# smart_home_demo.net
KiCad netlist of a schematic drawn in EAGLE
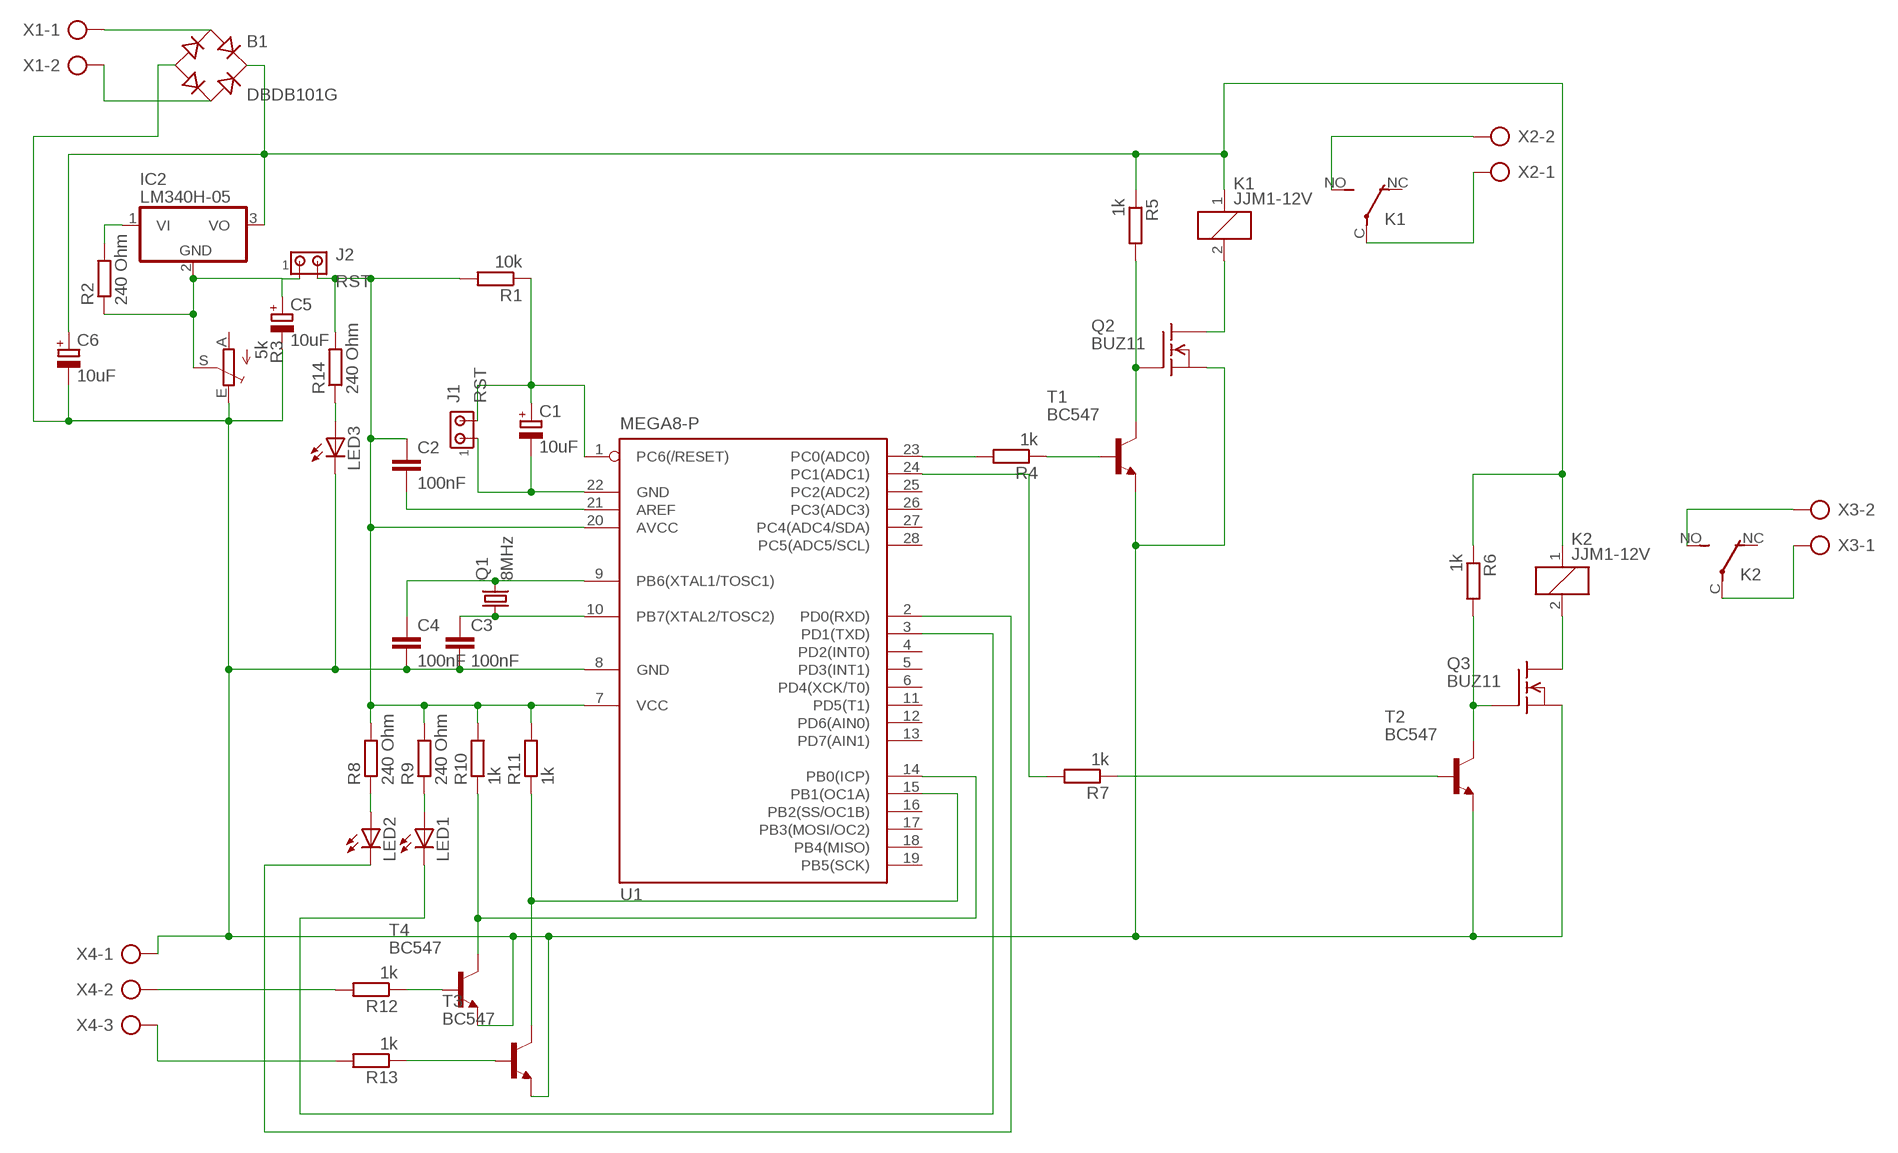
[diagram p0: schematic, sheet 1]

(export (version "E")
  (design (tool "Eeschema 10.0.6"))
  (components
    (comp (ref "B1")
      (value "DBDB101G")
      (footprint "eagle-import:DB")
      (libsource (lib "eagle-import") (part "DB?GDB101"))
    )
    (comp (ref "C1")
      (value "10uF")
      (footprint "eagle-import:E2,5-7")
      (libsource (lib "eagle-import") (part "CPOL-EUE2.5-7"))
    )
    (comp (ref "C2")
      (value "100nF")
      (footprint "eagle-import:C1206K")
      (libsource (lib "eagle-import") (part "C-EUC1206K"))
    )
    (comp (ref "C3")
      (value "100nF")
      (footprint "eagle-import:C1206K")
      (libsource (lib "eagle-import") (part "C-EUC1206K"))
    )
    (comp (ref "C4")
      (value "100nF")
      (footprint "eagle-import:C1206K")
      (libsource (lib "eagle-import") (part "C-EUC1206K"))
    )
    (comp (ref "C5")
      (value "10uF")
      (footprint "eagle-import:E2,5-7")
      (libsource (lib "eagle-import") (part "CPOL-EUE2.5-7"))
    )
    (comp (ref "C6")
      (value "10uF")
      (footprint "eagle-import:E2,5-7")
      (libsource (lib "eagle-import") (part "CPOL-EUE2.5-7"))
    )
    (comp (ref "IC2")
      (value "LM340H-05")
      (footprint "eagle-import:TO220H")
      (libsource (lib "eagle-import") (part "LM340?-H05"))
    )
    (comp (ref "J1")
      (value "RST")
      (footprint "eagle-import:10X02MTA")
      (libsource (lib "eagle-import") (part "MTA02-100"))
    )
    (comp (ref "J2")
      (value "RST")
      (footprint "eagle-import:10X02MTA")
      (libsource (lib "eagle-import") (part "MTA02-100"))
    )
    (comp (ref "K1")
      (value "JJM1-12V")
      (footprint "eagle-import:JJM1C")
      (fields (field (name "MF") "AROMAT/ MATSUSHITA"))
      (libsource (lib "eagle-import") (part "JJM1-12V"))
    )
    (comp (ref "K2")
      (value "JJM1-12V")
      (footprint "eagle-import:JJM1C")
      (fields (field (name "MF") "AROMAT/ MATSUSHITA"))
      (libsource (lib "eagle-import") (part "JJM1-12V"))
    )
    (comp (ref "LED1")
      (value "LED5MM")
      (footprint "eagle-import:LED5MM")
      (libsource (lib "eagle-import") (part "LED5MM"))
    )
    (comp (ref "LED2")
      (value "LED5MM")
      (footprint "eagle-import:LED5MM")
      (libsource (lib "eagle-import") (part "LED5MM"))
    )
    (comp (ref "LED3")
      (value "LED5MM")
      (footprint "eagle-import:LED5MM")
      (libsource (lib "eagle-import") (part "LED5MM"))
    )
    (comp (ref "Q1")
      (value "8MHz")
      (footprint "eagle-import:MC-405")
      (libsource (lib "eagle-import") (part "MC-405"))
    )
    (comp (ref "Q2")
      (value "BUZ11")
      (footprint "eagle-import:TO220")
      (libsource (lib "eagle-import") (part "BUZ11"))
    )
    (comp (ref "Q3")
      (value "BUZ11")
      (footprint "eagle-import:TO220")
      (libsource (lib "eagle-import") (part "BUZ11"))
    )
    (comp (ref "R1")
      (value "10k")
      (footprint "eagle-import:R1206")
      (libsource (lib "eagle-import") (part "R-EU_R1206"))
    )
    (comp (ref "R2")
      (value "240 Ohm")
      (footprint "eagle-import:R1206")
      (libsource (lib "eagle-import") (part "R-EU_R1206"))
    )
    (comp (ref "R3")
      (value "5k")
      (footprint "eagle-import:CA6V")
      (libsource (lib "eagle-import") (part "TRIM_EU-CA6V"))
    )
    (comp (ref "R4")
      (value "1k")
      (footprint "eagle-import:R1206")
      (libsource (lib "eagle-import") (part "R-EU_R1206"))
    )
    (comp (ref "R5")
      (value "1k")
      (footprint "eagle-import:R1206")
      (libsource (lib "eagle-import") (part "R-EU_R1206"))
    )
    (comp (ref "R6")
      (value "1k")
      (footprint "eagle-import:R1206")
      (libsource (lib "eagle-import") (part "R-EU_R1206"))
    )
    (comp (ref "R7")
      (value "1k")
      (footprint "eagle-import:R1206")
      (libsource (lib "eagle-import") (part "R-EU_R1206"))
    )
    (comp (ref "R8")
      (value "240 Ohm")
      (footprint "eagle-import:R1206")
      (libsource (lib "eagle-import") (part "R-EU_R1206"))
    )
    (comp (ref "R9")
      (value "240 Ohm")
      (footprint "eagle-import:R1206")
      (libsource (lib "eagle-import") (part "R-EU_R1206"))
    )
    (comp (ref "R10")
      (value "1k")
      (footprint "eagle-import:R1206")
      (libsource (lib "eagle-import") (part "R-EU_R1206"))
    )
    (comp (ref "R11")
      (value "1k")
      (footprint "eagle-import:R1206")
      (libsource (lib "eagle-import") (part "R-EU_R1206"))
    )
    (comp (ref "R12")
      (value "1k")
      (footprint "eagle-import:R1206")
      (libsource (lib "eagle-import") (part "R-EU_R1206"))
    )
    (comp (ref "R13")
      (value "1k")
      (footprint "eagle-import:R1206")
      (libsource (lib "eagle-import") (part "R-EU_R1206"))
    )
    (comp (ref "R14")
      (value "240 Ohm")
      (footprint "eagle-import:R1206")
      (libsource (lib "eagle-import") (part "R-EU_R1206"))
    )
    (comp (ref "T1")
      (value "BC547")
      (footprint "eagle-import:TO92")
      (libsource (lib "eagle-import") (part "BC547"))
    )
    (comp (ref "T2")
      (value "BC547")
      (footprint "eagle-import:TO92")
      (libsource (lib "eagle-import") (part "BC547"))
    )
    (comp (ref "T3")
      (value "BC547")
      (footprint "eagle-import:TO92")
      (libsource (lib "eagle-import") (part "BC547"))
    )
    (comp (ref "T4")
      (value "BC547")
      (footprint "eagle-import:TO92")
      (libsource (lib "eagle-import") (part "BC547"))
    )
    (comp (ref "U1")
      (value "MEGA8-P")
      (footprint "eagle-import:DIL28-3")
      (libsource (lib "eagle-import") (part "MEGA8-P"))
    )
    (comp (ref "X1")
      (value "AK300/2")
      (footprint "eagle-import:AK300_2")
      (libsource (lib "eagle-import") (part "AK300/2"))
    )
    (comp (ref "X2")
      (value "AK300/2")
      (footprint "eagle-import:AK300_2")
      (libsource (lib "eagle-import") (part "AK300/2"))
    )
    (comp (ref "X3")
      (value "AK300/2")
      (footprint "eagle-import:AK300_2")
      (libsource (lib "eagle-import") (part "AK300/2"))
    )
    (comp (ref "X4")
      (value "AK300/3")
      (footprint "eagle-import:AK300_3")
      (libsource (lib "eagle-import") (part "AK300/3"))
    )
  )
  (nets
    (net (code "1") (name "Net-(C1-Pad-)") (class "Default")
      (node (ref "C1") (pin "-") (pinfunction "-_-") (pintype "passive"))
      (node (ref "J1") (pin "1") (pinfunction "1_1") (pintype "passive"))
      (node (ref "U1") (pin "22") (pinfunction "GND_22") (pintype "power_in"))
    )
    (net (code "2") (name "Net-(IC2-GND)") (class "Default")
      (node (ref "C5") (pin "+") (pinfunction "+_+") (pintype "passive"))
      (node (ref "IC2") (pin "2") (pinfunction "GND_2") (pintype "passive"))
      (node (ref "J2") (pin "1") (pinfunction "1_1") (pintype "passive"))
      (node (ref "R2") (pin "1") (pinfunction "1_1") (pintype "passive"))
      (node (ref "R3") (pin "S") (pinfunction "S_S") (pintype "passive"))
    )
    (net (code "3") (name "Net-(IC2-VI)") (class "Default")
      (node (ref "IC2") (pin "1") (pinfunction "VI_1") (pintype "input"))
      (node (ref "R2") (pin "2") (pinfunction "2_2") (pintype "passive"))
    )
    (net (code "4") (name "Net-(IC2-VO)") (class "Default")
      (node (ref "B1") (pin "+") (pinfunction "+_+") (pintype "passive"))
      (node (ref "C6") (pin "+") (pinfunction "+_+") (pintype "passive"))
      (node (ref "IC2") (pin "3") (pinfunction "VO_3") (pintype "passive"))
      (node (ref "K1") (pin "1") (pinfunction "1_1") (pintype "passive"))
      (node (ref "K2") (pin "1") (pinfunction "1_1") (pintype "passive"))
      (node (ref "R5") (pin "1") (pinfunction "1_1") (pintype "passive"))
      (node (ref "R6") (pin "1") (pinfunction "1_1") (pintype "passive"))
    )
    (net (code "5") (name "Net-(K1B-P)") (class "Default")
      (node (ref "K1") (pin "C") (pinfunction "P_C") (pintype "passive"))
      (node (ref "X2") (pin "1") (pinfunction "KL_1") (pintype "passive"))
    )
    (net (code "6") (name "Net-(K1B-S)") (class "Default")
      (node (ref "K1") (pin "NO") (pinfunction "S_NO") (pintype "passive"))
      (node (ref "X2") (pin "2") (pinfunction "KL_2") (pintype "passive"))
    )
    (net (code "7") (name "Net-(K2B-P)") (class "Default")
      (node (ref "K2") (pin "C") (pinfunction "P_C") (pintype "passive"))
      (node (ref "X3") (pin "1") (pinfunction "KL_1") (pintype "passive"))
    )
    (net (code "8") (name "Net-(K2B-S)") (class "Default")
      (node (ref "K2") (pin "NO") (pinfunction "S_NO") (pintype "passive"))
      (node (ref "X3") (pin "2") (pinfunction "KL_2") (pintype "passive"))
    )
    (net (code "9") (name "Net-(LED1-C)") (class "Default")
      (node (ref "LED1") (pin "K") (pinfunction "C_K") (pintype "passive"))
      (node (ref "U1") (pin "3") (pinfunction "PD1(TXD)_3") (pintype "bidirectional"))
    )
    (net (code "10") (name "Net-(LED1-PadA)") (class "Default")
      (node (ref "LED1") (pin "A") (pinfunction "A_A") (pintype "passive"))
      (node (ref "R9") (pin "1") (pinfunction "1_1") (pintype "passive"))
    )
    (net (code "11") (name "Net-(LED2-C)") (class "Default")
      (node (ref "LED2") (pin "K") (pinfunction "C_K") (pintype "passive"))
      (node (ref "U1") (pin "2") (pinfunction "PD0(RXD)_2") (pintype "bidirectional"))
    )
    (net (code "12") (name "Net-(LED2-PadA)") (class "Default")
      (node (ref "LED2") (pin "A") (pinfunction "A_A") (pintype "passive"))
      (node (ref "R8") (pin "1") (pinfunction "1_1") (pintype "passive"))
    )
    (net (code "13") (name "Net-(LED3-C)") (class "Default")
      (node (ref "B1") (pin "-") (pinfunction "-_-") (pintype "passive"))
      (node (ref "C3") (pin "2") (pinfunction "2_2") (pintype "passive"))
      (node (ref "C4") (pin "2") (pinfunction "2_2") (pintype "passive"))
      (node (ref "C5") (pin "-") (pinfunction "-_-") (pintype "passive"))
      (node (ref "C6") (pin "-") (pinfunction "-_-") (pintype "passive"))
      (node (ref "LED3") (pin "K") (pinfunction "C_K") (pintype "passive"))
      (node (ref "Q2") (pin "3") (pinfunction "S_3") (pintype "passive"))
      (node (ref "Q3") (pin "3") (pinfunction "S_3") (pintype "passive"))
      (node (ref "R3") (pin "E") (pinfunction "E_E") (pintype "passive"))
      (node (ref "T1") (pin "1") (pinfunction "E_1") (pintype "passive"))
      (node (ref "T2") (pin "1") (pinfunction "E_1") (pintype "passive"))
      (node (ref "T3") (pin "1") (pinfunction "E_1") (pintype "passive"))
      (node (ref "T4") (pin "1") (pinfunction "E_1") (pintype "passive"))
      (node (ref "U1") (pin "8") (pinfunction "GND_8") (pintype "power_in"))
      (node (ref "X4") (pin "1") (pinfunction "KL_1") (pintype "passive"))
    )
    (net (code "14") (name "Net-(LED3-PadA)") (class "Default")
      (node (ref "LED3") (pin "A") (pinfunction "A_A") (pintype "passive"))
      (node (ref "R14") (pin "1") (pinfunction "1_1") (pintype "passive"))
    )
    (net (code "15") (name "Net-(Q2-D)") (class "Default")
      (node (ref "K1") (pin "2") (pinfunction "2_2") (pintype "passive"))
      (node (ref "Q2") (pin "2") (pinfunction "D_2") (pintype "passive"))
    )
    (net (code "16") (name "Net-(Q2-G)") (class "Default")
      (node (ref "Q2") (pin "1") (pinfunction "G_1") (pintype "passive"))
      (node (ref "R5") (pin "2") (pinfunction "2_2") (pintype "passive"))
      (node (ref "T1") (pin "3") (pinfunction "C_3") (pintype "passive"))
    )
    (net (code "17") (name "Net-(Q3-D)") (class "Default")
      (node (ref "K2") (pin "2") (pinfunction "2_2") (pintype "passive"))
      (node (ref "Q3") (pin "2") (pinfunction "D_2") (pintype "passive"))
    )
    (net (code "18") (name "Net-(Q3-G)") (class "Default")
      (node (ref "Q3") (pin "1") (pinfunction "G_1") (pintype "passive"))
      (node (ref "R6") (pin "2") (pinfunction "2_2") (pintype "passive"))
      (node (ref "T2") (pin "3") (pinfunction "C_3") (pintype "passive"))
    )
    (net (code "19") (name "Net-(T1-B)") (class "Default")
      (node (ref "R4") (pin "1") (pinfunction "1_1") (pintype "passive"))
      (node (ref "T1") (pin "2") (pinfunction "B_2") (pintype "passive"))
    )
    (net (code "20") (name "Net-(T2-B)") (class "Default")
      (node (ref "R7") (pin "1") (pinfunction "1_1") (pintype "passive"))
      (node (ref "T2") (pin "2") (pinfunction "B_2") (pintype "passive"))
    )
    (net (code "21") (name "Net-(T3-B)") (class "Default")
      (node (ref "R13") (pin "1") (pinfunction "1_1") (pintype "passive"))
      (node (ref "T3") (pin "2") (pinfunction "B_2") (pintype "passive"))
    )
    (net (code "22") (name "Net-(T3-C)") (class "Default")
      (node (ref "R11") (pin "1") (pinfunction "1_1") (pintype "passive"))
      (node (ref "T3") (pin "3") (pinfunction "C_3") (pintype "passive"))
      (node (ref "U1") (pin "15") (pinfunction "PB1(OC1A)_15") (pintype "bidirectional"))
    )
    (net (code "23") (name "Net-(T4-B)") (class "Default")
      (node (ref "R12") (pin "1") (pinfunction "1_1") (pintype "passive"))
      (node (ref "T4") (pin "2") (pinfunction "B_2") (pintype "passive"))
    )
    (net (code "24") (name "Net-(T4-C)") (class "Default")
      (node (ref "R10") (pin "1") (pinfunction "1_1") (pintype "passive"))
      (node (ref "T4") (pin "3") (pinfunction "C_3") (pintype "passive"))
      (node (ref "U1") (pin "14") (pinfunction "PB0(ICP)_14") (pintype "bidirectional"))
    )
    (net (code "25") (name "Net-(U1-AREF)") (class "Default")
      (node (ref "C2") (pin "2") (pinfunction "2_2") (pintype "passive"))
      (node (ref "U1") (pin "21") (pinfunction "AREF_21") (pintype "passive"))
    )
    (net (code "26") (name "Net-(U1-AVCC)") (class "Default")
      (node (ref "C2") (pin "1") (pinfunction "1_1") (pintype "passive"))
      (node (ref "J2") (pin "2") (pinfunction "2_2") (pintype "passive"))
      (node (ref "R1") (pin "2") (pinfunction "2_2") (pintype "passive"))
      (node (ref "R10") (pin "2") (pinfunction "2_2") (pintype "passive"))
      (node (ref "R11") (pin "2") (pinfunction "2_2") (pintype "passive"))
      (node (ref "R14") (pin "2") (pinfunction "2_2") (pintype "passive"))
      (node (ref "R8") (pin "2") (pinfunction "2_2") (pintype "passive"))
      (node (ref "R9") (pin "2") (pinfunction "2_2") (pintype "passive"))
      (node (ref "U1") (pin "20") (pinfunction "AVCC_20") (pintype "power_in"))
      (node (ref "U1") (pin "7") (pinfunction "VCC_7") (pintype "power_in"))
    )
    (net (code "27") (name "Net-(U1-PB6(XTAL1{slash}TOSC1))") (class "Default")
      (node (ref "C4") (pin "1") (pinfunction "1_1") (pintype "passive"))
      (node (ref "Q1") (pin "2") (pinfunction "2_2") (pintype "passive"))
      (node (ref "U1") (pin "9") (pinfunction "PB6(XTAL1/TOSC1)_9") (pintype "bidirectional"))
    )
    (net (code "28") (name "Net-(U1-PB7(XTAL2{slash}TOSC2))") (class "Default")
      (node (ref "C3") (pin "1") (pinfunction "1_1") (pintype "passive"))
      (node (ref "Q1") (pin "1") (pinfunction "1_1") (pintype "passive"))
      (node (ref "U1") (pin "10") (pinfunction "PB7(XTAL2/TOSC2)_10") (pintype "bidirectional"))
    )
    (net (code "29") (name "Net-(U1-PC0(ADC0))") (class "Default")
      (node (ref "R4") (pin "2") (pinfunction "2_2") (pintype "passive"))
      (node (ref "U1") (pin "23") (pinfunction "PC0(ADC0)_23") (pintype "bidirectional"))
    )
    (net (code "30") (name "Net-(U1-PC1(ADC1))") (class "Default")
      (node (ref "R7") (pin "2") (pinfunction "2_2") (pintype "passive"))
      (node (ref "U1") (pin "24") (pinfunction "PC1(ADC1)_24") (pintype "bidirectional"))
    )
    (net (code "31") (name "Net-(U1-PC6({slash}RESET))") (class "Default")
      (node (ref "C1") (pin "+") (pinfunction "+_+") (pintype "passive"))
      (node (ref "J1") (pin "2") (pinfunction "2_2") (pintype "passive"))
      (node (ref "R1") (pin "1") (pinfunction "1_1") (pintype "passive"))
      (node (ref "U1") (pin "1") (pinfunction "PC6(/RESET)_1") (pintype "bidirectional"))
    )
    (net (code "32") (name "Net-(X1A-KL)") (class "Default")
      (node (ref "B1") (pin "AC1") (pinfunction "AC1_AC1") (pintype "passive"))
      (node (ref "X1") (pin "1") (pinfunction "KL_1") (pintype "passive"))
    )
    (net (code "33") (name "Net-(X1B-KL)") (class "Default")
      (node (ref "B1") (pin "AC2") (pinfunction "AC2_AC2") (pintype "passive"))
      (node (ref "X1") (pin "2") (pinfunction "KL_2") (pintype "passive"))
    )
    (net (code "34") (name "Net-(X4B-KL)") (class "Default")
      (node (ref "R12") (pin "2") (pinfunction "2_2") (pintype "passive"))
      (node (ref "X4") (pin "2") (pinfunction "KL_2") (pintype "passive"))
    )
    (net (code "35") (name "Net-(X4C-KL)") (class "Default")
      (node (ref "R13") (pin "2") (pinfunction "2_2") (pintype "passive"))
      (node (ref "X4") (pin "3") (pinfunction "KL_3") (pintype "passive"))
    )
    (net (code "36") (name "unconnected-(K1B-O-PadNC)") (class "Default")
      (node (ref "K1") (pin "NC") (pinfunction "O_NC") (pintype "passive"))
    )
    (net (code "37") (name "unconnected-(K2B-O-PadNC)") (class "Default")
      (node (ref "K2") (pin "NC") (pinfunction "O_NC") (pintype "passive"))
    )
    (net (code "38") (name "unconnected-(R3-PadA)") (class "Default")
      (node (ref "R3") (pin "A") (pinfunction "A_A") (pintype "passive"))
    )
    (net (code "39") (name "unconnected-(U1-PB2(SS{slash}OC1B)-Pad16)") (class "Default")
      (node (ref "U1") (pin "16") (pinfunction "PB2(SS/OC1B)_16") (pintype "bidirectional"))
    )
    (net (code "40") (name "unconnected-(U1-PB3(MOSI{slash}OC2)-Pad17)") (class "Default")
      (node (ref "U1") (pin "17") (pinfunction "PB3(MOSI/OC2)_17") (pintype "bidirectional"))
    )
    (net (code "41") (name "unconnected-(U1-PB4(MISO)-Pad18)") (class "Default")
      (node (ref "U1") (pin "18") (pinfunction "PB4(MISO)_18") (pintype "bidirectional"))
    )
    (net (code "42") (name "unconnected-(U1-PB5(SCK)-Pad19)") (class "Default")
      (node (ref "U1") (pin "19") (pinfunction "PB5(SCK)_19") (pintype "bidirectional"))
    )
    (net (code "43") (name "unconnected-(U1-PC2(ADC2)-Pad25)") (class "Default")
      (node (ref "U1") (pin "25") (pinfunction "PC2(ADC2)_25") (pintype "bidirectional"))
    )
    (net (code "44") (name "unconnected-(U1-PC3(ADC3)-Pad26)") (class "Default")
      (node (ref "U1") (pin "26") (pinfunction "PC3(ADC3)_26") (pintype "bidirectional"))
    )
    (net (code "45") (name "unconnected-(U1-PC4(ADC4{slash}SDA)-Pad27)") (class "Default")
      (node (ref "U1") (pin "27") (pinfunction "PC4(ADC4/SDA)_27") (pintype "bidirectional"))
    )
    (net (code "46") (name "unconnected-(U1-PC5(ADC5{slash}SCL)-Pad28)") (class "Default")
      (node (ref "U1") (pin "28") (pinfunction "PC5(ADC5/SCL)_28") (pintype "bidirectional"))
    )
    (net (code "47") (name "unconnected-(U1-PD2(INT0)-Pad4)") (class "Default")
      (node (ref "U1") (pin "4") (pinfunction "PD2(INT0)_4") (pintype "bidirectional"))
    )
    (net (code "48") (name "unconnected-(U1-PD3(INT1)-Pad5)") (class "Default")
      (node (ref "U1") (pin "5") (pinfunction "PD3(INT1)_5") (pintype "bidirectional"))
    )
    (net (code "49") (name "unconnected-(U1-PD4(XCK{slash}T0)-Pad6)") (class "Default")
      (node (ref "U1") (pin "6") (pinfunction "PD4(XCK/T0)_6") (pintype "bidirectional"))
    )
    (net (code "50") (name "unconnected-(U1-PD5(T1)-Pad11)") (class "Default")
      (node (ref "U1") (pin "11") (pinfunction "PD5(T1)_11") (pintype "bidirectional"))
    )
    (net (code "51") (name "unconnected-(U1-PD6(AIN0)-Pad12)") (class "Default")
      (node (ref "U1") (pin "12") (pinfunction "PD6(AIN0)_12") (pintype "bidirectional"))
    )
    (net (code "52") (name "unconnected-(U1-PD7(AIN1)-Pad13)") (class "Default")
      (node (ref "U1") (pin "13") (pinfunction "PD7(AIN1)_13") (pintype "bidirectional"))
    )
  )
)
